# SCH_Genie-V1_2024-08-01.net
KiCad netlist of a schematic drawn in EasyEDA
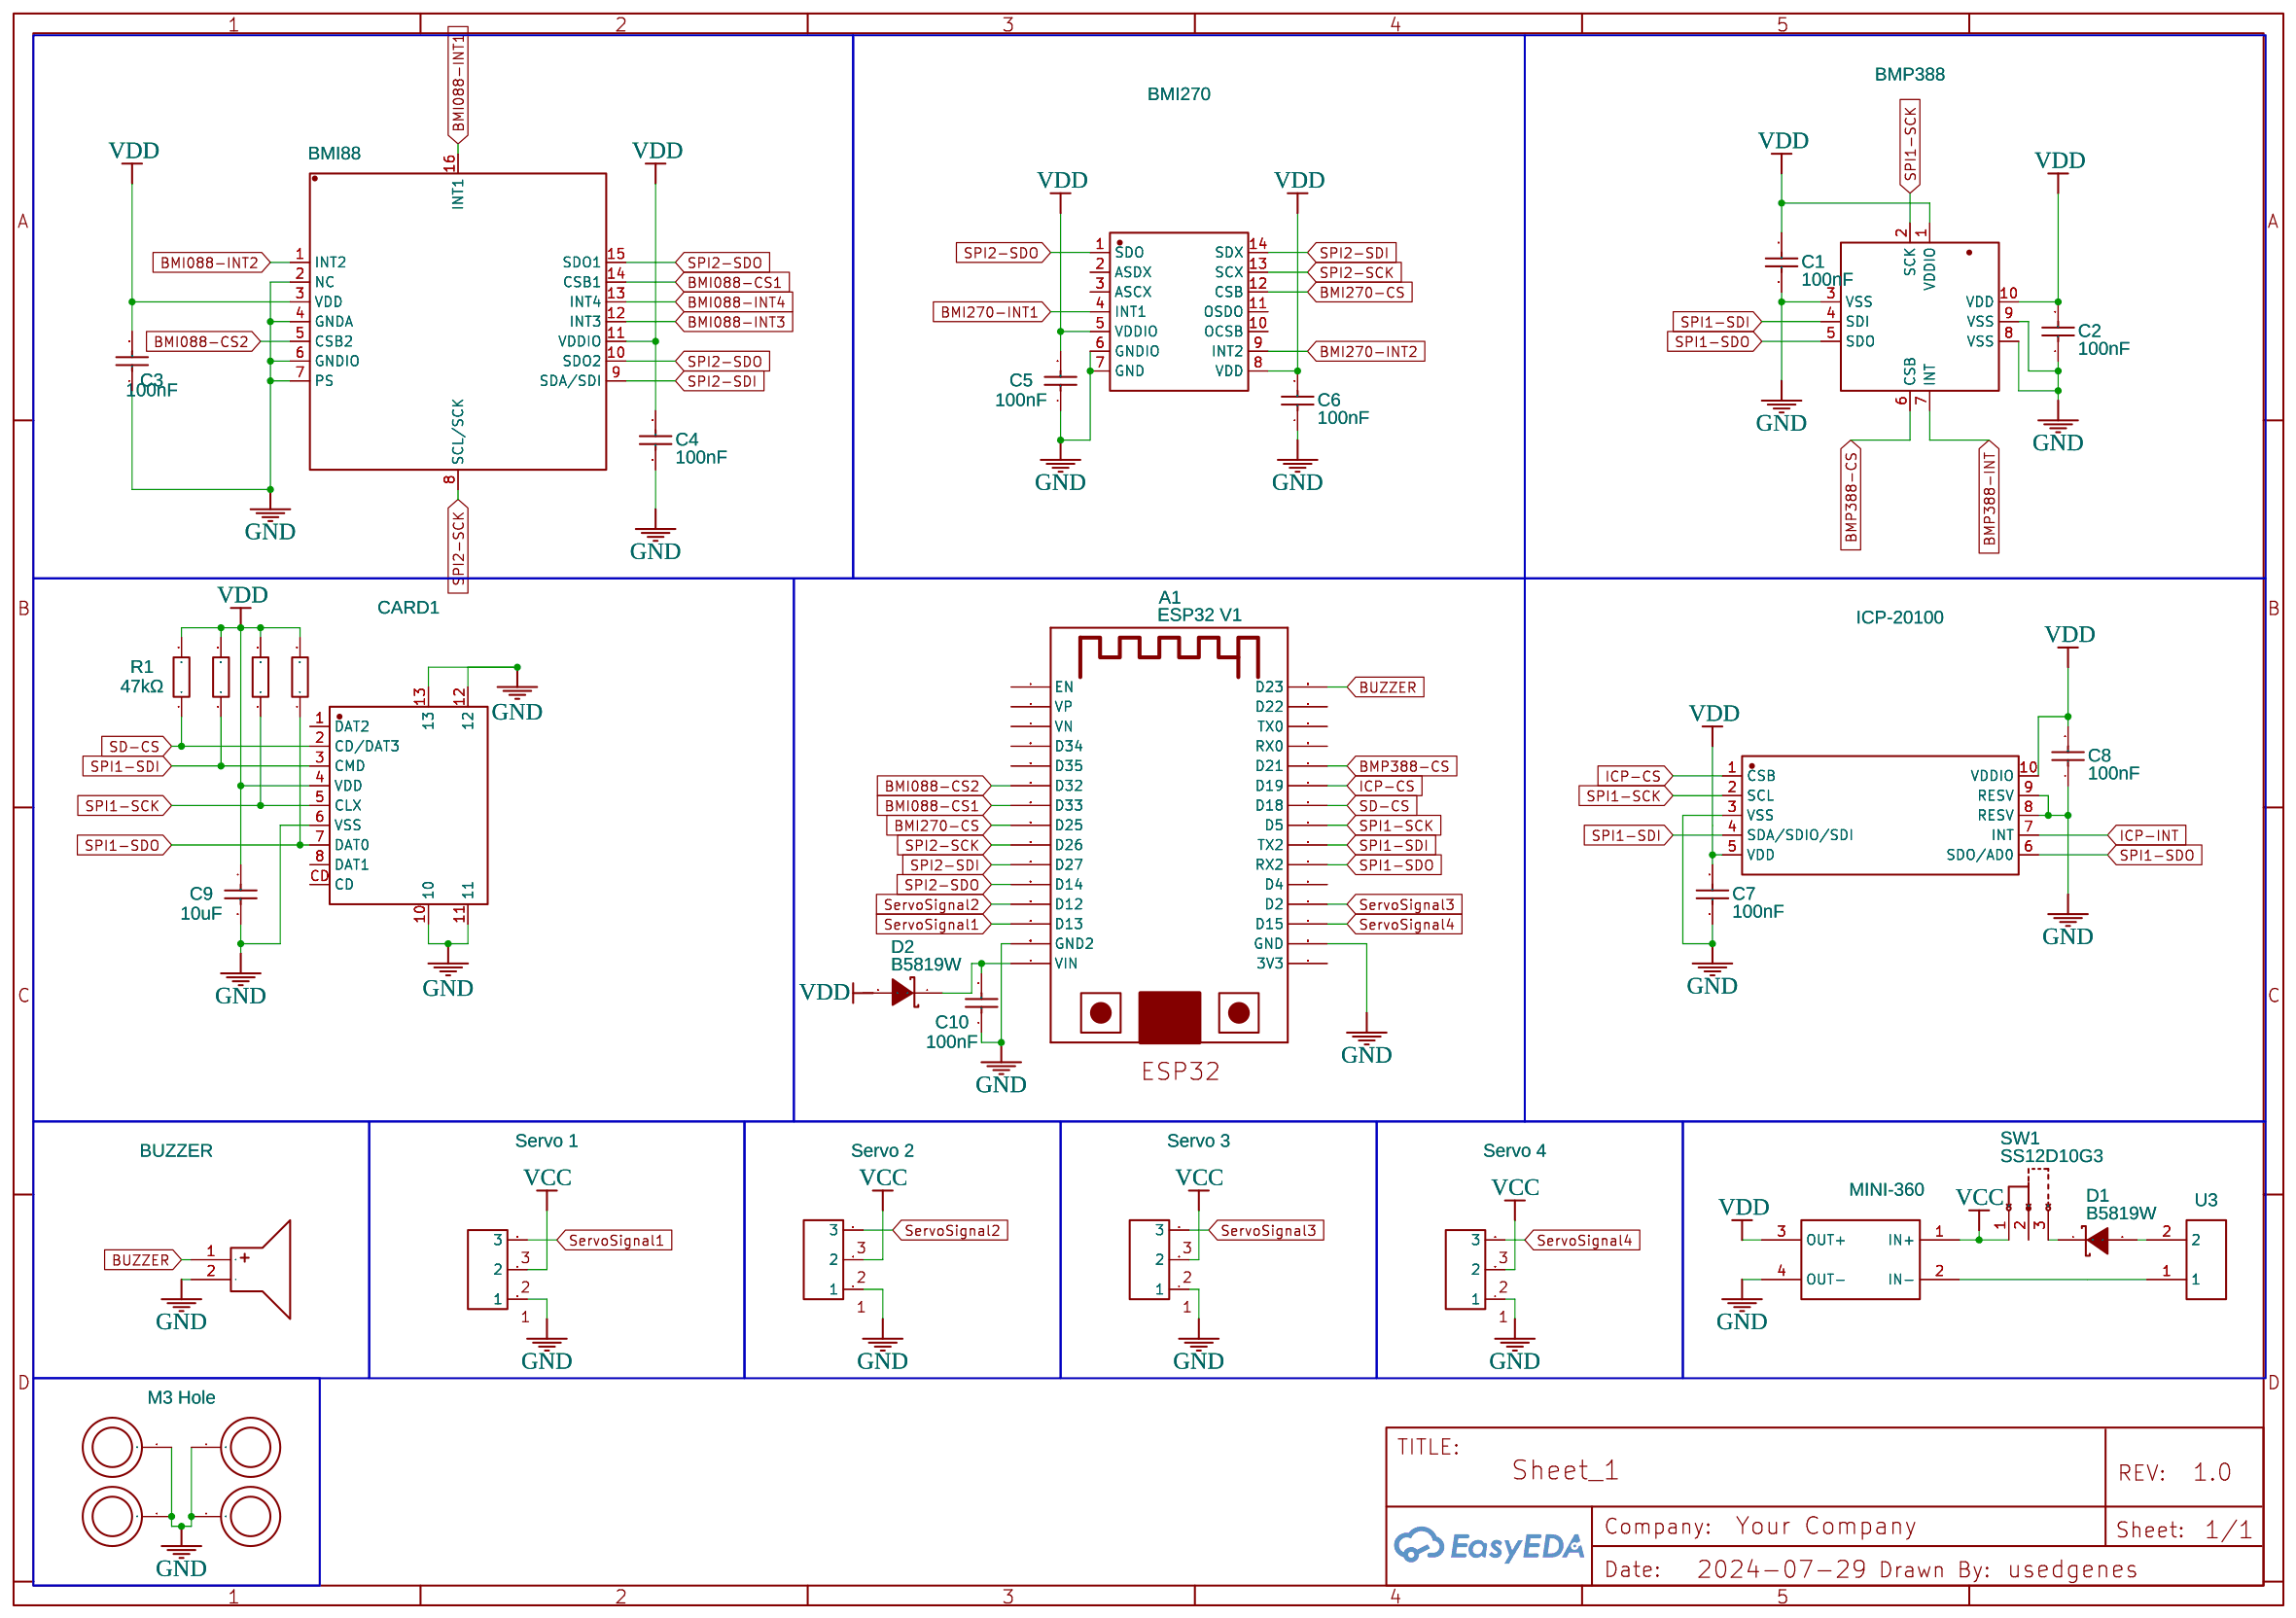
[diagram p0: schematic sheet]

(export (version "E")
  (design (tool "Eeschema 10.0.6"))
  (components
    (comp (ref "A1") (value "ESP32 V1") (libsource (lib "") (part "ESP32-DEVKIT-V1-30PIN")))
    (comp (ref "BMI88")
      (value "BMI088")
      (fields (field (name "Manufacturer") "Bosch(博世)"))
      (libsource (lib "") (part "BMI088"))
    )
    (comp (ref "BMI270")
      (value "BMI270")
      (fields (field (name "Manufacturer") "Bosch(博世)"))
      (libsource (lib "") (part "BMI270"))
    )
    (comp (ref "BMP388")
      (value "BMP388")
      (fields (field (name "Manufacturer") "Bosch(博世)"))
      (libsource (lib "") (part "BMP388"))
    )
    (comp (ref "BUZZER")
      (value "4000Hz")
      (fields
        (field (name "Manufacturer Part") "SKY-1475-0540-45P7.6")
        (field (name "Manufacturer") "S&S(海旭)")
      )
      (libsource (lib "") (part "SKY-1475-0540-45P7.6"))
    )
    (comp (ref "C1")
      (value "100nF")
      (fields
        (field (name "Manufacturer Part") "CL05B104KO5NNNC")
        (field (name "Manufacturer") "SAMSUNG(三星)")
      )
      (libsource (lib "") (part "CL05B104KO5NNNC"))
    )
    (comp (ref "C2")
      (value "100nF")
      (fields
        (field (name "Manufacturer Part") "CL05B104KO5NNNC")
        (field (name "Manufacturer") "SAMSUNG(三星)")
      )
      (libsource (lib "") (part "CL05B104KO5NNNC"))
    )
    (comp (ref "C3")
      (value "100nF")
      (fields
        (field (name "Manufacturer Part") "CL05B104KO5NNNC")
        (field (name "Manufacturer") "SAMSUNG(三星)")
      )
      (libsource (lib "") (part "CL05B104KO5NNNC"))
    )
    (comp (ref "C4")
      (value "100nF")
      (fields
        (field (name "Manufacturer Part") "CL05B104KO5NNNC")
        (field (name "Manufacturer") "SAMSUNG(三星)")
      )
      (libsource (lib "") (part "CL05B104KO5NNNC"))
    )
    (comp (ref "C5")
      (value "100nF")
      (fields
        (field (name "Manufacturer Part") "CL05B104KO5NNNC")
        (field (name "Manufacturer") "SAMSUNG(三星)")
      )
      (libsource (lib "") (part "CL05B104KO5NNNC"))
    )
    (comp (ref "C6")
      (value "100nF")
      (fields
        (field (name "Manufacturer Part") "CL05B104KO5NNNC")
        (field (name "Manufacturer") "SAMSUNG(三星)")
      )
      (libsource (lib "") (part "CL05B104KO5NNNC"))
    )
    (comp (ref "C7")
      (value "100nF")
      (fields
        (field (name "Manufacturer Part") "CL05B104KO5NNNC")
        (field (name "Manufacturer") "SAMSUNG(三星)")
      )
      (libsource (lib "") (part "CL05B104KO5NNNC"))
    )
    (comp (ref "C8")
      (value "100nF")
      (fields
        (field (name "Manufacturer Part") "CL05B104KO5NNNC")
        (field (name "Manufacturer") "SAMSUNG(三星)")
      )
      (libsource (lib "") (part "CL05B104KO5NNNC"))
    )
    (comp (ref "C9")
      (value "10uF")
      (fields
        (field (name "Manufacturer Part") "CL05A106MQ5NUNC")
        (field (name "Manufacturer") "SAMSUNG(三星)")
      )
      (libsource (lib "") (part "CL05A106MQ5NUNC"))
    )
    (comp (ref "C10")
      (value "100nF")
      (fields
        (field (name "Manufacturer Part") "CL05B104KO5NNNC")
        (field (name "Manufacturer") "SAMSUNG(三星)")
      )
      (libsource (lib "") (part "CL05B104KO5NNNC"))
    )
    (comp (ref "CARD1")
      (value "TF PUSH")
      (fields (field (name "Manufacturer") "SHOU HAN(首韩)"))
      (libsource (lib "") (part "TF PUSH"))
    )
    (comp (ref "D1")
      (value "B5819W")
      (fields (field (name "Manufacturer") "MDD(辰达半导体)"))
      (libsource (lib "") (part "B5819W_1"))
    )
    (comp (ref "D2")
      (value "B5819W")
      (fields (field (name "Manufacturer") "MDD(辰达半导体)"))
      (libsource (lib "") (part "B5819W"))
    )
    (comp (ref "H1") (value "M3 Hole") (libsource (lib "") (part "3MM_HOLE_1")))
    (comp (ref "H2") (value "3MM_HOLE") (libsource (lib "") (part "3MM_HOLE")))
    (comp (ref "H3") (value "3MM_HOLE") (libsource (lib "") (part "3MM_HOLE_1")))
    (comp (ref "H4") (value "3MM_HOLE") (libsource (lib "") (part "3MM_HOLE")))
    (comp (ref "ICP-20100")
      (value "ICP-20100")
      (fields (field (name "Manufacturer") "TDK"))
      (libsource (lib "") (part "ICP-20100"))
    )
    (comp (ref "MINI-360") (value "MINI-360") (libsource (lib "") (part "MINI-360")))
    (comp (ref "P1")
      (value "Servo 1")
      (fields
        (field (name "Manufacturer Part") "Female headerHDR1X8-2.54")
        (field (name "Manufacturer") "BOOMELE")
      )
      (libsource (lib "") (part "HEADER PAD 3X RMM COPY"))
    )
    (comp (ref "P2")
      (value "Servo 2")
      (fields
        (field (name "Manufacturer Part") "Female headerHDR1X8-2.54")
        (field (name "Manufacturer") "BOOMELE")
      )
      (libsource (lib "") (part "HEADER PAD 3X RMM COPY"))
    )
    (comp (ref "P3")
      (value "Servo 3")
      (fields
        (field (name "Manufacturer Part") "Female headerHDR1X8-2.54")
        (field (name "Manufacturer") "BOOMELE")
      )
      (libsource (lib "") (part "HEADER PAD 3X RMM COPY"))
    )
    (comp (ref "P4")
      (value "Servo 4")
      (fields
        (field (name "Manufacturer Part") "Female headerHDR1X8-2.54")
        (field (name "Manufacturer") "BOOMELE")
      )
      (libsource (lib "") (part "HEADER PAD 3X RMM COPY"))
    )
    (comp (ref "R1")
      (value "47kΩ")
      (fields
        (field (name "Manufacturer Part") "0402WGF4702TCE")
        (field (name "Manufacturer") "UNI-ROYAL(厚声)")
      )
      (libsource (lib "") (part "0402WGF4702TCE"))
    )
    (comp (ref "R2")
      (value "47kΩ")
      (fields
        (field (name "Manufacturer Part") "0402WGF4702TCE")
        (field (name "Manufacturer") "UNI-ROYAL(厚声)")
      )
      (libsource (lib "") (part "0402WGF4702TCE"))
    )
    (comp (ref "R3")
      (value "47kΩ")
      (fields
        (field (name "Manufacturer Part") "0402WGF4702TCE")
        (field (name "Manufacturer") "UNI-ROYAL(厚声)")
      )
      (libsource (lib "") (part "0402WGF4702TCE"))
    )
    (comp (ref "R4")
      (value "47kΩ")
      (fields
        (field (name "Manufacturer Part") "0402WGF4702TCE")
        (field (name "Manufacturer") "UNI-ROYAL(厚声)")
      )
      (libsource (lib "") (part "0402WGF4702TCE"))
    )
    (comp (ref "SW1")
      (value "SS12D10G3")
      (fields (field (name "Manufacturer") "SHOU HAN(首韩)"))
      (libsource (lib "") (part "SS12D10G3"))
    )
    (comp (ref "U3") (value "Power Pins") (libsource (lib "") (part "1X2")))
  )
  (nets
    (net (code "1") (name "BMI088-CS1") (class "Default")
      (node (ref "A1") (pin "D33") (pinfunction "D33_D33") (pintype "unspecified"))
      (node (ref "BMI88") (pin "14") (pinfunction "CSB1_14") (pintype "unspecified"))
    )
    (net (code "2") (name "BMI088-CS2") (class "Default")
      (node (ref "A1") (pin "D32") (pinfunction "D32_D32") (pintype "unspecified"))
      (node (ref "BMI88") (pin "5") (pinfunction "CSB2_5") (pintype "unspecified"))
    )
    (net (code "3") (name "BMI088-INT1") (class "Default")
      (node (ref "BMI88") (pin "16") (pinfunction "INT1_16") (pintype "unspecified"))
    )
    (net (code "4") (name "BMI088-INT2") (class "Default")
      (node (ref "BMI88") (pin "1") (pinfunction "INT2_1") (pintype "unspecified"))
    )
    (net (code "5") (name "BMI088-INT3") (class "Default")
      (node (ref "BMI88") (pin "12") (pinfunction "INT3_12") (pintype "unspecified"))
    )
    (net (code "6") (name "BMI088-INT4") (class "Default")
      (node (ref "BMI88") (pin "13") (pinfunction "INT4_13") (pintype "unspecified"))
    )
    (net (code "7") (name "BMI270-CS") (class "Default")
      (node (ref "A1") (pin "D25") (pinfunction "D25_D25") (pintype "unspecified"))
      (node (ref "BMI270") (pin "12") (pinfunction "CSB_12") (pintype "unspecified"))
    )
    (net (code "8") (name "BMI270-INT1") (class "Default")
      (node (ref "BMI270") (pin "4") (pinfunction "INT1_4") (pintype "unspecified"))
    )
    (net (code "9") (name "BMI270-INT2") (class "Default")
      (node (ref "BMI270") (pin "9") (pinfunction "INT2_9") (pintype "unspecified"))
    )
    (net (code "10") (name "BMP388-CS") (class "Default")
      (node (ref "A1") (pin "D21") (pinfunction "D21_D21") (pintype "unspecified"))
      (node (ref "BMP388") (pin "6") (pinfunction "CSB_6") (pintype "unspecified"))
    )
    (net (code "11") (name "BMP388-INT") (class "Default")
      (node (ref "BMP388") (pin "7") (pinfunction "INT_7") (pintype "unspecified"))
    )
    (net (code "12") (name "BUZZER") (class "Default")
      (node (ref "A1") (pin "D23") (pinfunction "D23_D23") (pintype "unspecified"))
      (node (ref "BUZZER") (pin "1") (pinfunction "+_1") (pintype "unspecified"))
    )
    (net (code "13") (name "GND") (class "Default")
      (node (ref "A1") (pin "GND") (pinfunction "GND_GND") (pintype "unspecified"))
      (node (ref "A1") (pin "GND2") (pinfunction "GND2_GND2") (pintype "unspecified"))
      (node (ref "BMI270") (pin "6") (pinfunction "GNDIO_6") (pintype "unspecified"))
      (node (ref "BMI270") (pin "7") (pinfunction "GND_7") (pintype "unspecified"))
      (node (ref "BMI88") (pin "2") (pinfunction "NC_2") (pintype "unspecified"))
      (node (ref "BMI88") (pin "4") (pinfunction "GNDA_4") (pintype "unspecified"))
      (node (ref "BMI88") (pin "6") (pinfunction "GNDIO_6") (pintype "unspecified"))
      (node (ref "BMI88") (pin "7") (pinfunction "PS_7") (pintype "unspecified"))
      (node (ref "BMP388") (pin "3") (pinfunction "VSS_3") (pintype "unspecified"))
      (node (ref "BMP388") (pin "8") (pinfunction "VSS_8") (pintype "unspecified"))
      (node (ref "BMP388") (pin "9") (pinfunction "VSS_9") (pintype "unspecified"))
      (node (ref "BUZZER") (pin "2") (pinfunction "-_2") (pintype "unspecified"))
      (node (ref "C1") (pin "1") (pinfunction "1_1") (pintype "input"))
      (node (ref "C10") (pin "1") (pinfunction "1_1") (pintype "input"))
      (node (ref "C2") (pin "1") (pinfunction "1_1") (pintype "input"))
      (node (ref "C3") (pin "1") (pinfunction "1_1") (pintype "input"))
      (node (ref "C4") (pin "1") (pinfunction "1_1") (pintype "input"))
      (node (ref "C5") (pin "1") (pinfunction "1_1") (pintype "input"))
      (node (ref "C6") (pin "1") (pinfunction "1_1") (pintype "input"))
      (node (ref "C7") (pin "1") (pinfunction "1_1") (pintype "input"))
      (node (ref "C8") (pin "1") (pinfunction "1_1") (pintype "input"))
      (node (ref "C9") (pin "2") (pinfunction "2_2") (pintype "input"))
      (node (ref "CARD1") (pin "10") (pinfunction "10_10") (pintype "unspecified"))
      (node (ref "CARD1") (pin "11") (pinfunction "11_11") (pintype "unspecified"))
      (node (ref "CARD1") (pin "12") (pinfunction "12_12") (pintype "unspecified"))
      (node (ref "CARD1") (pin "13") (pinfunction "13_13") (pintype "unspecified"))
      (node (ref "CARD1") (pin "6") (pinfunction "VSS_6") (pintype "unspecified"))
      (node (ref "H1") (pin "1") (pinfunction "1_1") (pintype "bidirectional"))
      (node (ref "H2") (pin "1") (pinfunction "1_1") (pintype "bidirectional"))
      (node (ref "H3") (pin "1") (pinfunction "1_1") (pintype "bidirectional"))
      (node (ref "H4") (pin "1") (pinfunction "1_1") (pintype "bidirectional"))
      (node (ref "ICP-20100") (pin "3") (pinfunction "VSS_3") (pintype "unspecified"))
      (node (ref "ICP-20100") (pin "8") (pinfunction "RESV_8") (pintype "unspecified"))
      (node (ref "ICP-20100") (pin "9") (pinfunction "RESV_9") (pintype "unspecified"))
      (node (ref "MINI-360") (pin "4") (pinfunction "OUT-_4") (pintype "unspecified"))
      (node (ref "P1") (pin "1") (pinfunction "1_1") (pintype "unspecified"))
      (node (ref "P2") (pin "1") (pinfunction "1_1") (pintype "unspecified"))
      (node (ref "P3") (pin "1") (pinfunction "1_1") (pintype "unspecified"))
      (node (ref "P4") (pin "1") (pinfunction "1_1") (pintype "unspecified"))
    )
    (net (code "14") (name "ICP-CS") (class "Default")
      (node (ref "A1") (pin "D19") (pinfunction "D19_D19") (pintype "unspecified"))
      (node (ref "ICP-20100") (pin "1") (pinfunction "CSB_1") (pintype "unspecified"))
    )
    (net (code "15") (name "ICP-INT") (class "Default")
      (node (ref "ICP-20100") (pin "7") (pinfunction "INT_7") (pintype "unspecified"))
    )
    (net (code "16") (name "Net-(D1-A)") (class "Default")
      (node (ref "D1") (pin "2") (pinfunction "A_2") (pintype "unspecified"))
      (node (ref "U3") (pin "2") (pinfunction "2_2") (pintype "unspecified"))
    )
    (net (code "17") (name "Net-(D1-K)") (class "Default")
      (node (ref "D1") (pin "1") (pinfunction "K_1") (pintype "unspecified"))
      (node (ref "SW1") (pin "3") (pinfunction "3_3") (pintype "unspecified"))
    )
    (net (code "18") (name "Net-(D2-K)") (class "Default")
      (node (ref "A1") (pin "VIN") (pinfunction "VIN_VIN") (pintype "unspecified"))
      (node (ref "C10") (pin "2") (pinfunction "2_2") (pintype "input"))
      (node (ref "D2") (pin "1") (pinfunction "K_1") (pintype "unspecified"))
    )
    (net (code "19") (name "Net-(MINI-360-IN-)") (class "Default")
      (node (ref "MINI-360") (pin "2") (pinfunction "IN-_2") (pintype "unspecified"))
      (node (ref "U3") (pin "1") (pinfunction "1_1") (pintype "unspecified"))
    )
    (net (code "20") (name "SD-CS") (class "Default")
      (node (ref "A1") (pin "D18") (pinfunction "D18_D18") (pintype "unspecified"))
      (node (ref "CARD1") (pin "2") (pinfunction "CD/DAT3_2") (pintype "unspecified"))
      (node (ref "R1") (pin "1") (pinfunction "1_1") (pintype "input"))
    )
    (net (code "21") (name "SPI1-SCK") (class "Default")
      (node (ref "A1") (pin "D5") (pinfunction "D5_D5") (pintype "unspecified"))
      (node (ref "BMP388") (pin "2") (pinfunction "SCK_2") (pintype "unspecified"))
      (node (ref "CARD1") (pin "5") (pinfunction "CLX_5") (pintype "unspecified"))
      (node (ref "ICP-20100") (pin "2") (pinfunction "SCL_2") (pintype "unspecified"))
      (node (ref "R3") (pin "1") (pinfunction "1_1") (pintype "input"))
    )
    (net (code "22") (name "SPI1-SDI") (class "Default")
      (node (ref "A1") (pin "TX2") (pinfunction "TX2_TX2") (pintype "unspecified"))
      (node (ref "BMP388") (pin "4") (pinfunction "SDI_4") (pintype "unspecified"))
      (node (ref "CARD1") (pin "3") (pinfunction "CMD_3") (pintype "unspecified"))
      (node (ref "ICP-20100") (pin "4") (pinfunction "SDA/SDIO/SDI_4") (pintype "unspecified"))
      (node (ref "R2") (pin "1") (pinfunction "1_1") (pintype "input"))
    )
    (net (code "23") (name "SPI1-SDO") (class "Default")
      (node (ref "A1") (pin "RX2") (pinfunction "RX2_RX2") (pintype "unspecified"))
      (node (ref "BMP388") (pin "5") (pinfunction "SDO_5") (pintype "unspecified"))
      (node (ref "CARD1") (pin "7") (pinfunction "DAT0_7") (pintype "unspecified"))
      (node (ref "ICP-20100") (pin "6") (pinfunction "SDO/AD0_6") (pintype "unspecified"))
      (node (ref "R4") (pin "1") (pinfunction "1_1") (pintype "input"))
    )
    (net (code "24") (name "SPI2-SCK") (class "Default")
      (node (ref "A1") (pin "D26") (pinfunction "D26_D26") (pintype "unspecified"))
      (node (ref "BMI270") (pin "13") (pinfunction "SCX_13") (pintype "unspecified"))
      (node (ref "BMI88") (pin "8") (pinfunction "SCL/SCK_8") (pintype "unspecified"))
    )
    (net (code "25") (name "SPI2-SDI") (class "Default")
      (node (ref "A1") (pin "D27") (pinfunction "D27_D27") (pintype "unspecified"))
      (node (ref "BMI270") (pin "14") (pinfunction "SDX_14") (pintype "unspecified"))
      (node (ref "BMI88") (pin "9") (pinfunction "SDA/SDI_9") (pintype "unspecified"))
    )
    (net (code "26") (name "SPI2-SDO") (class "Default")
      (node (ref "A1") (pin "D14") (pinfunction "D14_D14") (pintype "unspecified"))
      (node (ref "BMI270") (pin "1") (pinfunction "SDO_1") (pintype "unspecified"))
      (node (ref "BMI88") (pin "10") (pinfunction "SDO2_10") (pintype "unspecified"))
      (node (ref "BMI88") (pin "15") (pinfunction "SDO1_15") (pintype "unspecified"))
    )
    (net (code "27") (name "ServoSignal1") (class "Default")
      (node (ref "A1") (pin "D13") (pinfunction "D13_D13") (pintype "unspecified"))
      (node (ref "P1") (pin "3") (pinfunction "3_3") (pintype "unspecified"))
    )
    (net (code "28") (name "ServoSignal2") (class "Default")
      (node (ref "A1") (pin "D12") (pinfunction "D12_D12") (pintype "unspecified"))
      (node (ref "P2") (pin "3") (pinfunction "3_3") (pintype "unspecified"))
    )
    (net (code "29") (name "ServoSignal3") (class "Default")
      (node (ref "A1") (pin "D2") (pinfunction "D2_D2") (pintype "unspecified"))
      (node (ref "P3") (pin "3") (pinfunction "3_3") (pintype "unspecified"))
    )
    (net (code "30") (name "ServoSignal4") (class "Default")
      (node (ref "A1") (pin "D15") (pinfunction "D15_D15") (pintype "unspecified"))
      (node (ref "P4") (pin "3") (pinfunction "3_3") (pintype "unspecified"))
    )
    (net (code "31") (name "VCC") (class "Default")
      (node (ref "MINI-360") (pin "1") (pinfunction "IN+_1") (pintype "unspecified"))
      (node (ref "P1") (pin "2") (pinfunction "2_2") (pintype "unspecified"))
      (node (ref "P2") (pin "2") (pinfunction "2_2") (pintype "unspecified"))
      (node (ref "P3") (pin "2") (pinfunction "2_2") (pintype "unspecified"))
      (node (ref "P4") (pin "2") (pinfunction "2_2") (pintype "unspecified"))
      (node (ref "SW1") (pin "1") (pinfunction "1_1") (pintype "unspecified"))
    )
    (net (code "32") (name "VDD") (class "Default")
      (node (ref "BMI270") (pin "5") (pinfunction "VDDIO_5") (pintype "unspecified"))
      (node (ref "BMI270") (pin "8") (pinfunction "VDD_8") (pintype "unspecified"))
      (node (ref "BMI88") (pin "11") (pinfunction "VDDIO_11") (pintype "unspecified"))
      (node (ref "BMI88") (pin "3") (pinfunction "VDD_3") (pintype "unspecified"))
      (node (ref "BMP388") (pin "1") (pinfunction "VDDIO_1") (pintype "unspecified"))
      (node (ref "BMP388") (pin "10") (pinfunction "VDD_10") (pintype "unspecified"))
      (node (ref "C1") (pin "2") (pinfunction "2_2") (pintype "input"))
      (node (ref "C2") (pin "2") (pinfunction "2_2") (pintype "input"))
      (node (ref "C3") (pin "2") (pinfunction "2_2") (pintype "input"))
      (node (ref "C4") (pin "2") (pinfunction "2_2") (pintype "input"))
      (node (ref "C5") (pin "2") (pinfunction "2_2") (pintype "input"))
      (node (ref "C6") (pin "2") (pinfunction "2_2") (pintype "input"))
      (node (ref "C7") (pin "2") (pinfunction "2_2") (pintype "input"))
      (node (ref "C8") (pin "2") (pinfunction "2_2") (pintype "input"))
      (node (ref "C9") (pin "1") (pinfunction "1_1") (pintype "input"))
      (node (ref "CARD1") (pin "4") (pinfunction "VDD_4") (pintype "unspecified"))
      (node (ref "D2") (pin "2") (pinfunction "A_2") (pintype "unspecified"))
      (node (ref "ICP-20100") (pin "10") (pinfunction "VDDIO_10") (pintype "unspecified"))
      (node (ref "ICP-20100") (pin "5") (pinfunction "VDD_5") (pintype "unspecified"))
      (node (ref "MINI-360") (pin "3") (pinfunction "OUT+_3") (pintype "unspecified"))
      (node (ref "R1") (pin "2") (pinfunction "2_2") (pintype "input"))
      (node (ref "R2") (pin "2") (pinfunction "2_2") (pintype "input"))
      (node (ref "R3") (pin "2") (pinfunction "2_2") (pintype "input"))
      (node (ref "R4") (pin "2") (pinfunction "2_2") (pintype "input"))
    )
    (net (code "33") (name "unconnected-(A1-Pad3V3)") (class "Default")
      (node (ref "A1") (pin "3V3") (pinfunction "3V3_3V3") (pintype "unspecified"))
    )
    (net (code "34") (name "unconnected-(A1-PadD4)") (class "Default")
      (node (ref "A1") (pin "D4") (pinfunction "D4_D4") (pintype "unspecified"))
    )
    (net (code "35") (name "unconnected-(A1-PadD22)") (class "Default")
      (node (ref "A1") (pin "D22") (pinfunction "D22_D22") (pintype "unspecified"))
    )
    (net (code "36") (name "unconnected-(A1-PadD34)") (class "Default")
      (node (ref "A1") (pin "D34") (pinfunction "D34_D34") (pintype "unspecified"))
    )
    (net (code "37") (name "unconnected-(A1-PadD35)") (class "Default")
      (node (ref "A1") (pin "D35") (pinfunction "D35_D35") (pintype "unspecified"))
    )
    (net (code "38") (name "unconnected-(A1-PadEN)") (class "Default")
      (node (ref "A1") (pin "EN") (pinfunction "EN_EN") (pintype "unspecified"))
    )
    (net (code "39") (name "unconnected-(A1-PadRX0)") (class "Default")
      (node (ref "A1") (pin "RX0") (pinfunction "RX0_RX0") (pintype "unspecified"))
    )
    (net (code "40") (name "unconnected-(A1-PadTX0)") (class "Default")
      (node (ref "A1") (pin "TX0") (pinfunction "TX0_TX0") (pintype "unspecified"))
    )
    (net (code "41") (name "unconnected-(A1-PadVN)") (class "Default")
      (node (ref "A1") (pin "VN") (pinfunction "VN_VN") (pintype "unspecified"))
    )
    (net (code "42") (name "unconnected-(A1-PadVP)") (class "Default")
      (node (ref "A1") (pin "VP") (pinfunction "VP_VP") (pintype "unspecified"))
    )
    (net (code "43") (name "unconnected-(BMI270-ASCX-Pad3)") (class "Default")
      (node (ref "BMI270") (pin "3") (pinfunction "ASCX_3") (pintype "unspecified"))
    )
    (net (code "44") (name "unconnected-(BMI270-ASDX-Pad2)") (class "Default")
      (node (ref "BMI270") (pin "2") (pinfunction "ASDX_2") (pintype "unspecified"))
    )
    (net (code "45") (name "unconnected-(BMI270-OCSB-Pad10)") (class "Default")
      (node (ref "BMI270") (pin "10") (pinfunction "OCSB_10") (pintype "unspecified"))
    )
    (net (code "46") (name "unconnected-(BMI270-OSDO-Pad11)") (class "Default")
      (node (ref "BMI270") (pin "11") (pinfunction "OSDO_11") (pintype "unspecified"))
    )
    (net (code "47") (name "unconnected-(CARD1-DAT1-Pad8)") (class "Default")
      (node (ref "CARD1") (pin "8") (pinfunction "DAT1_8") (pintype "unspecified"))
    )
    (net (code "48") (name "unconnected-(CARD1-DAT2-Pad1)") (class "Default")
      (node (ref "CARD1") (pin "1") (pinfunction "DAT2_1") (pintype "unspecified"))
    )
    (net (code "49") (name "unconnected-(CARD1-PadCD)") (class "Default")
      (node (ref "CARD1") (pin "CD") (pinfunction "CD_CD") (pintype "unspecified"))
    )
    (net (code "50") (name "unconnected-(SW1-Pad2)") (class "Default")
      (node (ref "SW1") (pin "2") (pinfunction "2_2") (pintype "unspecified"))
    )
  )
)
